# ft61f14x_test.net
KiCad netlist of a schematic drawn in Altium Designer
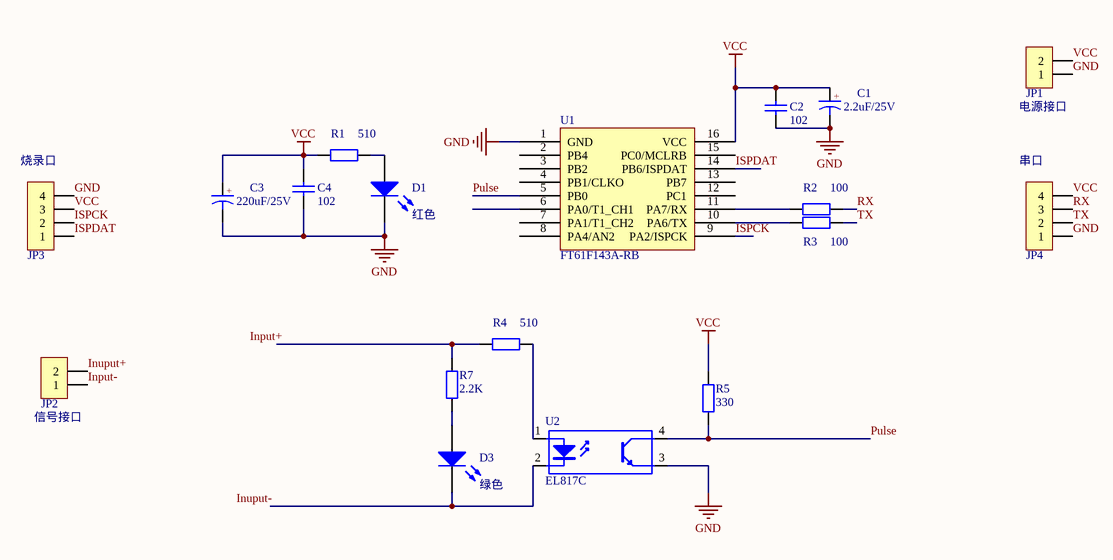
[diagram p0: ft61f14x_test.SchDoc]

(export (version "E")
  (design (tool "Eeschema 10.0.6"))
  (components
    (comp (ref "C1")
      (value "2.2uF/25V")
      (footprint "CE-1.5*4*8")
      (description "直插电解电容")
      (libsource (lib "0.1 - 电阻-电容-电感-保险丝-晶振-晶体-磁珠-电位器-法拉电容-馈通电容") (part "CE"))
    )
    (comp (ref "C2")
      (value "102")
      (footprint "C0805_L")
      (description "贴片电容/MLCC电容")
      (libsource (lib "0.1 - 电阻-电容-电感-保险丝-晶振-晶体-磁珠-电位器-法拉电容-馈通电容") (part "C"))
    )
    (comp (ref "C3")
      (value "220uF/25V")
      (footprint "CE-1.5*4*8")
      (description "直插电解电容")
      (libsource (lib "0.1 - 电阻-电容-电感-保险丝-晶振-晶体-磁珠-电位器-法拉电容-馈通电容") (part "CE"))
    )
    (comp (ref "C4")
      (value "102")
      (footprint "C0805_L")
      (description "贴片电容/MLCC电容")
      (libsource (lib "0.1 - 电阻-电容-电感-保险丝-晶振-晶体-磁珠-电位器-法拉电容-馈通电容") (part "C"))
    )
    (comp (ref "D1")
      (value "红色")
      (footprint "LED0805_G")
      (description "贴片LED")
      (libsource (lib "0.3 - LED发光二极管-IR二极管_接收管-光耦") (part "LED"))
    )
    (comp (ref "D3")
      (value "绿色")
      (footprint "LED0805_G")
      (description "贴片LED")
      (libsource (lib "0.3 - LED发光二极管-IR二极管_接收管-光耦") (part "LED"))
    )
    (comp (ref "JP1")
      (value "HDR-1X2")
      (footprint "XH2.54-LI-2P")
      (description "2P接插件")
      (libsource (lib "5.5 - 2.54mm连接器(KF2EDGK_XH2.54_2.54排针排母)") (part "Header 2"))
    )
    (comp (ref "JP2")
      (value "HDR-1X2")
      (footprint "XH2.54-LI-2P")
      (description "2P接插件")
      (libsource (lib "5.5 - 2.54mm连接器(KF2EDGK_XH2.54_2.54排针排母)") (part "Header 2"))
    )
    (comp (ref "JP3")
      (value "HDR-1X4")
      (footprint "XH2.54-LI-4P")
      (description "4P接插件")
      (libsource (lib "5.5 - 2.54mm连接器(KF2EDGK_XH2.54_2.54排针排母)") (part "Header 4"))
    )
    (comp (ref "JP4")
      (value "HDR-1X4")
      (footprint "XH2.54-LI-4P")
      (description "4P接插件")
      (libsource (lib "5.5 - 2.54mm连接器(KF2EDGK_XH2.54_2.54排针排母)") (part "Header 4"))
    )
    (comp (ref "R1")
      (value "510")
      (footprint "R0805_L")
      (description "贴片电阻")
      (libsource (lib "0.1 - 电阻-电容-电感-保险丝-晶振-晶体-磁珠-电位器-法拉电容-馈通电容") (part "R"))
    )
    (comp (ref "R2")
      (value "100")
      (footprint "R0805_L")
      (description "贴片电阻")
      (libsource (lib "0.1 - 电阻-电容-电感-保险丝-晶振-晶体-磁珠-电位器-法拉电容-馈通电容") (part "R"))
    )
    (comp (ref "R3")
      (value "100")
      (footprint "R0805_L")
      (description "贴片电阻")
      (libsource (lib "0.1 - 电阻-电容-电感-保险丝-晶振-晶体-磁珠-电位器-法拉电容-馈通电容") (part "R"))
    )
    (comp (ref "R4")
      (value "510")
      (footprint "R0805_L")
      (description "贴片电阻")
      (libsource (lib "0.1 - 电阻-电容-电感-保险丝-晶振-晶体-磁珠-电位器-法拉电容-馈通电容") (part "R"))
    )
    (comp (ref "R5")
      (value "330")
      (footprint "R0805_L")
      (description "贴片电阻")
      (libsource (lib "0.1 - 电阻-电容-电感-保险丝-晶振-晶体-磁珠-电位器-法拉电容-馈通电容") (part "R"))
    )
    (comp (ref "R7")
      (value "2.2K")
      (footprint "R0805_L")
      (description "贴片电阻")
      (libsource (lib "0.1 - 电阻-电容-电感-保险丝-晶振-晶体-磁珠-电位器-法拉电容-馈通电容") (part "R"))
    )
    (comp (ref "U1")
      (value "FT61F143A-RB")
      (footprint "2.11-SO封装:SO14")
      (libsource (lib "S05-IC") (part "FT61F143A-RB"))
    )
    (comp (ref "U2")
      (value "EL817C")
      (footprint "DIP-4")
      (description "4-Pin Phototransistor Optocoupler")
      (fields (field (name "PUBLISHER") "Altium Limited"))
      (libsource (lib "Miscellaneous Devices") (part "Optoisolator1"))
    )
  )
  (nets
    (net (code "1") (name "/ISPCK") (class "Default")
      (node (ref "JP3") (pin "2") (pinfunction "2_2") (pintype "passive"))
      (node (ref "U1") (pin "9") (pinfunction "PA2/ISPCK_9") (pintype "passive"))
    )
    (net (code "2") (name "/ISPDAT") (class "Default")
      (node (ref "JP3") (pin "1") (pinfunction "1_1") (pintype "passive"))
      (node (ref "U1") (pin "14") (pinfunction "PB6/ISPDAT_14") (pintype "passive"))
    )
    (net (code "4") (name "/Input-") (class "Default")
      (node (ref "JP2") (pin "1") (pinfunction "1_1") (pintype "passive"))
    )
    (net (code "5") (name "/Inuput+") (class "Default")
      (node (ref "JP2") (pin "2") (pinfunction "2_2") (pintype "passive"))
    )
    (net (code "7") (name "/Pulse") (class "Default")
      (node (ref "R5") (pin "1") (pinfunction "1_1") (pintype "passive"))
      (node (ref "U1") (pin "5") (pinfunction "PB0_5") (pintype "passive"))
      (node (ref "U2") (pin "4") (pinfunction "C_4") (pintype "passive"))
    )
    (net (code "8") (name "/RX") (class "Default")
      (node (ref "JP4") (pin "3") (pinfunction "3_3") (pintype "passive"))
      (node (ref "R2") (pin "1") (pinfunction "1_1") (pintype "passive"))
    )
    (net (code "9") (name "/TX") (class "Default")
      (node (ref "JP4") (pin "2") (pinfunction "2_2") (pintype "passive"))
      (node (ref "R3") (pin "1") (pinfunction "1_1") (pintype "passive"))
    )
    (net (code "10") (name "GND") (class "Default")
      (node (ref "C1") (pin "2") (pinfunction "2_2") (pintype "passive"))
      (node (ref "C2") (pin "1") (pinfunction "1_1") (pintype "passive"))
      (node (ref "C3") (pin "2") (pinfunction "2_2") (pintype "passive"))
      (node (ref "C4") (pin "1") (pinfunction "1_1") (pintype "passive"))
      (node (ref "D1") (pin "2") (pinfunction "K_2") (pintype "passive"))
      (node (ref "JP1") (pin "1") (pinfunction "1_1") (pintype "passive"))
      (node (ref "JP3") (pin "4") (pinfunction "4_4") (pintype "passive"))
      (node (ref "JP4") (pin "1") (pinfunction "1_1") (pintype "passive"))
      (node (ref "U1") (pin "1") (pinfunction "GND_1") (pintype "passive"))
      (node (ref "U2") (pin "3") (pinfunction "E_3") (pintype "passive"))
    )
    (net (code "11") (name "Net-(D1-A)") (class "Default")
      (node (ref "D1") (pin "1") (pinfunction "A_1") (pintype "passive"))
      (node (ref "R1") (pin "2") (pinfunction "2_2") (pintype "passive"))
    )
    (net (code "12") (name "Net-(D3-A)") (class "Default")
      (node (ref "D3") (pin "1") (pinfunction "A_1") (pintype "passive"))
      (node (ref "R7") (pin "2") (pinfunction "2_2") (pintype "passive"))
    )
    (net (code "13") (name "Net-(D3-K)") (class "Default")
      (node (ref "D3") (pin "2") (pinfunction "K_2") (pintype "passive"))
      (node (ref "U2") (pin "2") (pinfunction "K_2") (pintype "passive"))
    )
    (net (code "14") (name "Net-(R4-Pad1)") (class "Default")
      (node (ref "R4") (pin "1") (pinfunction "1_1") (pintype "passive"))
      (node (ref "R7") (pin "1") (pinfunction "1_1") (pintype "passive"))
    )
    (net (code "15") (name "Net-(U1-PA6{slash}TX)") (class "Default")
      (node (ref "R3") (pin "2") (pinfunction "2_2") (pintype "passive"))
      (node (ref "U1") (pin "10") (pinfunction "PA6/TX_10") (pintype "passive"))
    )
    (net (code "16") (name "Net-(U1-PA7{slash}RX)") (class "Default")
      (node (ref "R2") (pin "2") (pinfunction "2_2") (pintype "passive"))
      (node (ref "U1") (pin "11") (pinfunction "PA7/RX_11") (pintype "passive"))
    )
    (net (code "17") (name "Net-(U2-A)") (class "Default")
      (node (ref "R4") (pin "2") (pinfunction "2_2") (pintype "passive"))
      (node (ref "U2") (pin "1") (pinfunction "A_1") (pintype "passive"))
    )
    (net (code "18") (name "VCC") (class "Default")
      (node (ref "C1") (pin "1") (pinfunction "1_1") (pintype "passive"))
      (node (ref "C2") (pin "2") (pinfunction "2_2") (pintype "passive"))
      (node (ref "C3") (pin "1") (pinfunction "1_1") (pintype "passive"))
      (node (ref "C4") (pin "2") (pinfunction "2_2") (pintype "passive"))
      (node (ref "JP1") (pin "2") (pinfunction "2_2") (pintype "passive"))
      (node (ref "JP3") (pin "3") (pinfunction "3_3") (pintype "passive"))
      (node (ref "JP4") (pin "4") (pinfunction "4_4") (pintype "passive"))
      (node (ref "R1") (pin "1") (pinfunction "1_1") (pintype "passive"))
      (node (ref "R5") (pin "2") (pinfunction "2_2") (pintype "passive"))
      (node (ref "U1") (pin "16") (pinfunction "VCC_16") (pintype "passive"))
    )
    (net (code "19") (name "unconnected-(U1-PA0{slash}T1_CH1-Pad6)") (class "Default")
      (node (ref "U1") (pin "6") (pinfunction "PA0/T1_CH1_6") (pintype "passive"))
    )
    (net (code "20") (name "unconnected-(U1-PA1{slash}T1_CH2-Pad7)") (class "Default")
      (node (ref "U1") (pin "7") (pinfunction "PA1/T1_CH2_7") (pintype "passive"))
    )
    (net (code "21") (name "unconnected-(U1-PA4{slash}AN2-Pad8)") (class "Default")
      (node (ref "U1") (pin "8") (pinfunction "PA4/AN2_8") (pintype "passive"))
    )
    (net (code "22") (name "unconnected-(U1-PB1{slash}CLKO-Pad4)") (class "Default")
      (node (ref "U1") (pin "4") (pinfunction "PB1/CLKO_4") (pintype "passive"))
    )
    (net (code "23") (name "unconnected-(U1-PB2-Pad3)") (class "Default")
      (node (ref "U1") (pin "3") (pinfunction "PB2_3") (pintype "passive"))
    )
    (net (code "24") (name "unconnected-(U1-PB4-Pad2)") (class "Default")
      (node (ref "U1") (pin "2") (pinfunction "PB4_2") (pintype "passive"))
    )
    (net (code "25") (name "unconnected-(U1-PB7-Pad13)") (class "Default")
      (node (ref "U1") (pin "13") (pinfunction "PB7_13") (pintype "passive"))
    )
    (net (code "26") (name "unconnected-(U1-PC0{slash}MCLRB-Pad15)") (class "Default")
      (node (ref "U1") (pin "15") (pinfunction "PC0/MCLRB_15") (pintype "passive"))
    )
    (net (code "27") (name "unconnected-(U1-PC1-Pad12)") (class "Default")
      (node (ref "U1") (pin "12") (pinfunction "PC1_12") (pintype "passive"))
    )
  )
)
